# USB3_0_INTERFACE.net
KiCad netlist of a schematic drawn in Altium Designer
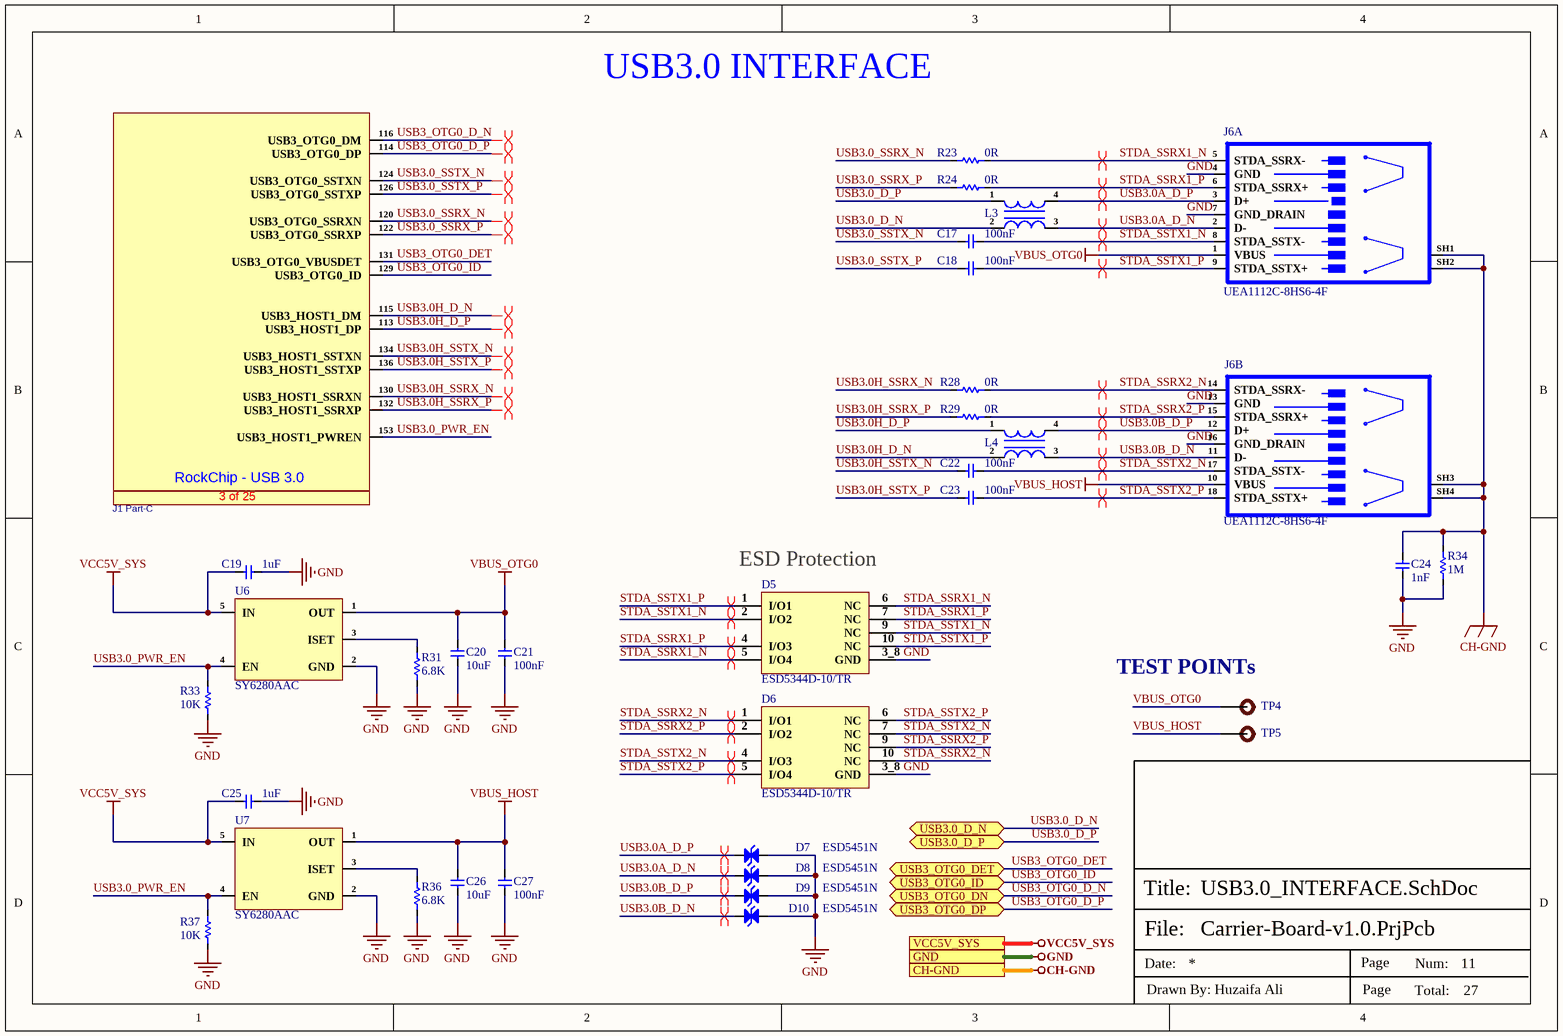
[diagram p0: USB3.0_INTERFACE.SchDoc]

(export (version "E")
  (design (tool "Eeschema 10.0.6"))
  (components
    (comp (ref "C17")
      (value "100nF")
      (footprint "Cap-0402")
      (description "CAP CER 0.1UF 16V X5R 0402")
      (fields
        (field (name "MANUFACTURER") "Yageo")
        (field (name "MANUFACTURER PART NUMBER") "CC0402KRX5R7BB104")
      )
      (libsource (lib "eSpark Libraries") (part "CC0402KRX5R7BB104"))
    )
    (comp (ref "C18")
      (value "100nF")
      (footprint "Cap-0402")
      (description "CAP CER 0.1UF 16V X5R 0402")
      (fields
        (field (name "MANUFACTURER") "Yageo")
        (field (name "MANUFACTURER PART NUMBER") "CC0402KRX5R7BB104")
      )
      (libsource (lib "eSpark Libraries") (part "CC0402KRX5R7BB104"))
    )
    (comp (ref "C19")
      (value "1uF")
      (footprint "Cap-0402")
      (description "CAP CER 1UF 16V X5R 0402")
      (fields
        (field (name "MANUFACTURER") "Yageo")
        (field (name "MANUFACTURER PART NUMBER") "CC0402KRX5R7BB105")
      )
      (libsource (lib "eSpark Libraries") (part "CC0402KRX5R7BB105"))
    )
    (comp (ref "C20")
      (value "10uF")
      (footprint "Cap-0603")
      (description "CAP CER 10UF 16V X5R 0603")
      (fields
        (field (name "MANUFACTURER") "Yageo")
        (field (name "MANUFACTURER PART NUMBER") "CC0603KRX5R7BB106")
      )
      (libsource (lib "eSpark Libraries") (part "CC0603KRX5R7BB106"))
    )
    (comp (ref "C21")
      (value "100nF")
      (footprint "Cap-0402")
      (description "CAP CER 0.1UF 16V X5R 0402")
      (fields
        (field (name "MANUFACTURER") "Yageo")
        (field (name "MANUFACTURER PART NUMBER") "CC0402KRX5R7BB104")
      )
      (libsource (lib "eSpark Libraries") (part "CC0402KRX5R7BB104"))
    )
    (comp (ref "C22")
      (value "100nF")
      (footprint "Cap-0402")
      (description "CAP CER 0.1UF 16V X5R 0402")
      (fields
        (field (name "MANUFACTURER") "Yageo")
        (field (name "MANUFACTURER PART NUMBER") "CC0402KRX5R7BB104")
      )
      (libsource (lib "eSpark Libraries") (part "CC0402KRX5R7BB104"))
    )
    (comp (ref "C23")
      (value "100nF")
      (footprint "Cap-0402")
      (description "CAP CER 0.1UF 16V X5R 0402")
      (fields
        (field (name "MANUFACTURER") "Yageo")
        (field (name "MANUFACTURER PART NUMBER") "CC0402KRX5R7BB104")
      )
      (libsource (lib "eSpark Libraries") (part "CC0402KRX5R7BB104"))
    )
    (comp (ref "C24")
      (value "1nF")
      (footprint "Cap-1206")
      (description "CAP CER 1000PF 2KV X7R 1206")
      (fields
        (field (name "MANUFACTURER") "Yageo")
        (field (name "MANUFACTURER PART NUMBER") "CC1206KKX7RDBB102")
      )
      (libsource (lib "eSpark Libraries") (part "CC1206KKX7RDBB102"))
    )
    (comp (ref "C25")
      (value "1uF")
      (footprint "Cap-0402")
      (description "CAP CER 1UF 16V X5R 0402")
      (fields
        (field (name "MANUFACTURER") "Yageo")
        (field (name "MANUFACTURER PART NUMBER") "CC0402KRX5R7BB105")
      )
      (libsource (lib "eSpark Libraries") (part "CC0402KRX5R7BB105"))
    )
    (comp (ref "C26")
      (value "10uF")
      (footprint "Cap-0603")
      (description "CAP CER 10UF 16V X5R 0603")
      (fields
        (field (name "MANUFACTURER") "Yageo")
        (field (name "MANUFACTURER PART NUMBER") "CC0603KRX5R7BB106")
      )
      (libsource (lib "eSpark Libraries") (part "CC0603KRX5R7BB106"))
    )
    (comp (ref "C27")
      (value "100nF")
      (footprint "Cap-0402")
      (description "CAP CER 0.1UF 16V X5R 0402")
      (fields
        (field (name "MANUFACTURER") "Yageo")
        (field (name "MANUFACTURER PART NUMBER") "CC0402KRX5R7BB104")
      )
      (libsource (lib "eSpark Libraries") (part "CC0402KRX5R7BB104"))
    )
    (comp (ref "D5")
      (value "ESD5344D-10/TR")
      (footprint "DFN2510-10L_")
      (description "DFN2510-10L ESD Protection Devices ROHS")
      (fields (field (name "MANUFACTURER") "WILLSEMI") (field (name "LCSC PART NUMBER") "C239666"))
      (libsource (lib "eSpark Libraries") (part "ESD5344D-10/TR"))
    )
    (comp (ref "D6")
      (value "ESD5344D-10/TR")
      (footprint "DFN2510-10L_")
      (description "DFN2510-10L ESD Protection Devices ROHS")
      (fields (field (name "MANUFACTURER") "WILLSEMI") (field (name "LCSC PART NUMBER") "C239666"))
      (libsource (lib "eSpark Libraries") (part "ESD5344D-10/TR"))
    )
    (comp (ref "D7")
      (value "ESD5451N")
      (footprint "DFN1006-2L (Bi-Directional)")
      (description "DFN1006-2(0402) ESD Protection Devices ROHS")
      (fields (field (name "MANUFACTURER") "TECH PUBLIC") (field (name "LCSC PART NUMBER") "C2936977"))
      (libsource (lib "Diode%") (part "ESD5451N"))
    )
    (comp (ref "D8")
      (value "ESD5451N")
      (footprint "DFN1006-2L (Bi-Directional)")
      (description "DFN1006-2(0402) ESD Protection Devices ROHS")
      (fields (field (name "MANUFACTURER") "TECH PUBLIC") (field (name "LCSC PART NUMBER") "C2936977"))
      (libsource (lib "Diode%") (part "ESD5451N"))
    )
    (comp (ref "D9")
      (value "ESD5451N")
      (footprint "DFN1006-2L (Bi-Directional)")
      (description "DFN1006-2(0402) ESD Protection Devices ROHS")
      (fields (field (name "MANUFACTURER") "TECH PUBLIC") (field (name "LCSC PART NUMBER") "C2936977"))
      (libsource (lib "Diode%") (part "ESD5451N"))
    )
    (comp (ref "D10")
      (value "ESD5451N")
      (footprint "DFN1006-2L (Bi-Directional)")
      (description "DFN1006-2(0402) ESD Protection Devices ROHS")
      (fields (field (name "MANUFACTURER") "TECH PUBLIC") (field (name "LCSC PART NUMBER") "C2936977"))
      (libsource (lib "Diode%") (part "ESD5451N"))
    )
    (comp (ref "J1 Part-")
      (value "AS0B826-S78B-7H")
      (footprint "AS0B826-S78B-7H")
      (description "SMD,P=0.5mm,Surface Mount，Right Angle")
      (fields (field (name "MANUFACTURER") "FOXCONN") (field (name "LCSC PART NUMBER") "C426232"))
      (libsource (lib "eSpark Libraries") (part "AS0B826-S78B-7H"))
    )
    (comp (ref "J6")
      (value "UEA1112C-8HS6-4F")
      (footprint "UEA1112C-8HS6-4F")
      (description "USB 3.0 2 Right-Angle 9P+9P Female Type-A Plugin USB Connectors ROHS")
      (fields (field (name "MANUFACTURER") "FOXCONN") (field (name "LCSC PART NUMBER") "C225759"))
      (libsource (lib "eSpark Libraries") (part "UEA1112C-8HS6-4F"))
    )
    (comp (ref "L3")
      (value "MCZ1210CH900L2TA0G")
      (footprint "MCZ1210CH900L2")
      (description "CMC 100MA 2LN 90 OHM SMD")
      (fields (field (name "MANUFACTURER") "TDK") (field (name "LCSC PART NUMBER") "C307688"))
      (libsource (lib "eSpark Libraries") (part "MCZ1210CH900L2TA0G"))
    )
    (comp (ref "L4")
      (value "MCZ1210CH900L2TA0G")
      (footprint "MCZ1210CH900L2")
      (description "CMC 100MA 2LN 90 OHM SMD")
      (fields (field (name "MANUFACTURER") "TDK") (field (name "LCSC PART NUMBER") "C307688"))
      (libsource (lib "eSpark Libraries") (part "MCZ1210CH900L2TA0G"))
    )
    (comp (ref "R23")
      (value "0R")
      (footprint "Res-0402")
      (description "RES 0 OHM JUMPER 1/16W 0402")
      (fields
        (field (name "MANUFACTURER") "Yageo")
        (field (name "MANUFACTURER PART NUMBER") "RC0402FR-070RL")
      )
      (libsource (lib "eSpark Libraries") (part "RC0402FR-070RL"))
    )
    (comp (ref "R24")
      (value "0R")
      (footprint "Res-0402")
      (description "RES 0 OHM JUMPER 1/16W 0402")
      (fields
        (field (name "MANUFACTURER") "Yageo")
        (field (name "MANUFACTURER PART NUMBER") "RC0402FR-070RL")
      )
      (libsource (lib "eSpark Libraries") (part "RC0402FR-070RL"))
    )
    (comp (ref "R28")
      (value "0R")
      (footprint "Res-0402")
      (description "RES 0 OHM JUMPER 1/16W 0402")
      (fields
        (field (name "MANUFACTURER") "Yageo")
        (field (name "MANUFACTURER PART NUMBER") "RC0402FR-070RL")
      )
      (libsource (lib "eSpark Libraries") (part "RC0402FR-070RL"))
    )
    (comp (ref "R29")
      (value "0R")
      (footprint "Res-0402")
      (description "RES 0 OHM JUMPER 1/16W 0402")
      (fields
        (field (name "MANUFACTURER") "Yageo")
        (field (name "MANUFACTURER PART NUMBER") "RC0402FR-070RL")
      )
      (libsource (lib "eSpark Libraries") (part "RC0402FR-070RL"))
    )
    (comp (ref "R31")
      (value "6.8K")
      (footprint "Res-0402")
      (description "RES 6.8K OHM 1% 1/16W 0402")
      (fields
        (field (name "MANUFACTURER") "Yageo")
        (field (name "MANUFACTURER PART NUMBER") "RC0402FR-076K8L")
      )
      (libsource (lib "eSpark Libraries") (part "RC0402FR-076K8L"))
    )
    (comp (ref "R33")
      (value "10K")
      (footprint "Res-0402")
      (description "RES 10K OHM 1% 1/16W 0402")
      (fields
        (field (name "MANUFACTURER") "Yageo")
        (field (name "MANUFACTURER PART NUMBER") "RC0402FR-0710KL")
      )
      (libsource (lib "eSpark Libraries") (part "RC0402FR-0710KL"))
    )
    (comp (ref "R34")
      (value "1M")
      (footprint "Res-0402")
      (description "RES SMD 1M OHM 5% 1/16W 0402")
      (fields
        (field (name "MANUFACTURER") "Yageo")
        (field (name "MANUFACTURER PART NUMBER") "AF0402JR-071ML")
      )
      (libsource (lib "eSpark Libraries") (part "AF0402JR-071ML"))
    )
    (comp (ref "R36")
      (value "6.8K")
      (footprint "Res-0402")
      (description "RES 6.8K OHM 1% 1/16W 0402")
      (fields
        (field (name "MANUFACTURER") "Yageo")
        (field (name "MANUFACTURER PART NUMBER") "RC0402FR-076K8L")
      )
      (libsource (lib "eSpark Libraries") (part "RC0402FR-076K8L"))
    )
    (comp (ref "R37")
      (value "10K")
      (footprint "Res-0402")
      (description "RES 10K OHM 1% 1/16W 0402")
      (fields
        (field (name "MANUFACTURER") "Yageo")
        (field (name "MANUFACTURER PART NUMBER") "RC0402FR-0710KL")
      )
      (libsource (lib "eSpark Libraries") (part "RC0402FR-0710KL"))
    )
    (comp (ref "TP4")
      (value "TEST POINT 0.5mm Dia")
      (footprint "Test-point - 0.5mm")
      (description "Test Point ON")
      (libsource (lib "eSpark Libraries") (part "TEST POINT 0.5mm Dia"))
    )
    (comp (ref "TP5")
      (value "TEST POINT 0.5mm Dia")
      (footprint "Test-point - 0.5mm")
      (description "Test Point ON")
      (libsource (lib "eSpark Libraries") (part "TEST POINT 0.5mm Dia"))
    )
    (comp (ref "U6")
      (value "SY6280AAC")
      (footprint "SOT-23-5")
      (description "SOT-23-5 Power Distribution Switches ROHS")
      (fields (field (name "MANUFACTURER") "Silergy") (field (name "LCSC PART NUMBER") "C55136"))
      (libsource (lib "eSpark Libraries") (part "SY6280AAC"))
    )
    (comp (ref "U7")
      (value "SY6280AAC")
      (footprint "SOT-23-5")
      (description "SOT-23-5 Power Distribution Switches ROHS")
      (fields (field (name "MANUFACTURER") "Silergy") (field (name "LCSC PART NUMBER") "C55136"))
      (libsource (lib "eSpark Libraries") (part "SY6280AAC"))
    )
  )
  (nets
    (net (code "1") (name "/STDA_SSRX1_N") (class "Default")
      (node (ref "D5") (pin "5") (pinfunction "I/O4_5") (pintype "passive"))
      (node (ref "D5") (pin "6") (pinfunction "NC_6") (pintype "passive"))
      (node (ref "J6") (pin "5") (pinfunction "STDA_SSRX-_5") (pintype "passive"))
      (node (ref "R23") (pin "2") (pinfunction "2_2") (pintype "passive"))
    )
    (net (code "2") (name "/STDA_SSRX1_P") (class "Default")
      (node (ref "D5") (pin "4") (pinfunction "I/O3_4") (pintype "passive"))
      (node (ref "D5") (pin "7") (pinfunction "NC_7") (pintype "passive"))
      (node (ref "J6") (pin "6") (pinfunction "STDA_SSRX+_6") (pintype "passive"))
      (node (ref "R24") (pin "2") (pinfunction "2_2") (pintype "passive"))
    )
    (net (code "3") (name "/STDA_SSRX2_N") (class "Default")
      (node (ref "D6") (pin "1") (pinfunction "I/O1_1") (pintype "passive"))
      (node (ref "D6") (pin "10") (pinfunction "NC_10") (pintype "passive"))
      (node (ref "J6") (pin "14") (pinfunction "STDA_SSRX-_14") (pintype "passive"))
      (node (ref "R28") (pin "2") (pinfunction "2_2") (pintype "passive"))
    )
    (net (code "4") (name "/STDA_SSRX2_P") (class "Default")
      (node (ref "D6") (pin "2") (pinfunction "I/O2_2") (pintype "passive"))
      (node (ref "D6") (pin "9") (pinfunction "NC_9") (pintype "passive"))
      (node (ref "J6") (pin "15") (pinfunction "STDA_SSRX+_15") (pintype "passive"))
      (node (ref "R29") (pin "2") (pinfunction "2_2") (pintype "passive"))
    )
    (net (code "5") (name "/STDA_SSTX1_N") (class "Default")
      (node (ref "C17") (pin "1") (pinfunction "1_1") (pintype "passive"))
      (node (ref "D5") (pin "2") (pinfunction "I/O2_2") (pintype "passive"))
      (node (ref "D5") (pin "9") (pinfunction "NC_9") (pintype "passive"))
      (node (ref "J6") (pin "8") (pinfunction "STDA_SSTX-_8") (pintype "passive"))
    )
    (net (code "6") (name "/STDA_SSTX1_P") (class "Default")
      (node (ref "C18") (pin "1") (pinfunction "1_1") (pintype "passive"))
      (node (ref "D5") (pin "1") (pinfunction "I/O1_1") (pintype "passive"))
      (node (ref "D5") (pin "10") (pinfunction "NC_10") (pintype "passive"))
      (node (ref "J6") (pin "9") (pinfunction "STDA_SSTX+_9") (pintype "passive"))
    )
    (net (code "7") (name "/STDA_SSTX2_N") (class "Default")
      (node (ref "C22") (pin "1") (pinfunction "1_1") (pintype "passive"))
      (node (ref "D6") (pin "4") (pinfunction "I/O3_4") (pintype "passive"))
      (node (ref "D6") (pin "7") (pinfunction "NC_7") (pintype "passive"))
      (node (ref "J6") (pin "17") (pinfunction "STDA_SSTX-_17") (pintype "passive"))
    )
    (net (code "8") (name "/STDA_SSTX2_P") (class "Default")
      (node (ref "C23") (pin "1") (pinfunction "1_1") (pintype "passive"))
      (node (ref "D6") (pin "5") (pinfunction "I/O4_5") (pintype "passive"))
      (node (ref "D6") (pin "6") (pinfunction "NC_6") (pintype "passive"))
      (node (ref "J6") (pin "18") (pinfunction "STDA_SSTX+_18") (pintype "passive"))
    )
    (net (code "9") (name "/USB3.0A_D_N") (class "Default")
      (node (ref "D8") (pin "2") (pinfunction "K_2") (pintype "passive"))
      (node (ref "J6") (pin "2") (pinfunction "D-_2") (pintype "passive"))
      (node (ref "L3") (pin "3") (pinfunction "3_3") (pintype "passive"))
    )
    (net (code "10") (name "/USB3.0A_D_P") (class "Default")
      (node (ref "D7") (pin "2") (pinfunction "K_2") (pintype "passive"))
      (node (ref "J6") (pin "3") (pinfunction "D+_3") (pintype "passive"))
      (node (ref "L3") (pin "4") (pinfunction "4_4") (pintype "passive"))
    )
    (net (code "11") (name "/USB3.0B_D_N") (class "Default")
      (node (ref "D10") (pin "2") (pinfunction "K_2") (pintype "passive"))
      (node (ref "J6") (pin "11") (pinfunction "D-_11") (pintype "passive"))
      (node (ref "L4") (pin "3") (pinfunction "3_3") (pintype "passive"))
    )
    (net (code "12") (name "/USB3.0B_D_P") (class "Default")
      (node (ref "D9") (pin "2") (pinfunction "K_2") (pintype "passive"))
      (node (ref "J6") (pin "12") (pinfunction "D+_12") (pintype "passive"))
      (node (ref "L4") (pin "4") (pinfunction "4_4") (pintype "passive"))
    )
    (net (code "13") (name "/USB3.0H_D_N") (class "Default")
      (node (ref "J1 Part-") (pin "115") (pinfunction "USB3_HOST1_DM_115") (pintype "passive"))
      (node (ref "L4") (pin "2") (pinfunction "2_2") (pintype "passive"))
    )
    (net (code "14") (name "/USB3.0H_D_P") (class "Default")
      (node (ref "J1 Part-") (pin "113") (pinfunction "USB3_HOST1_DP_113") (pintype "passive"))
      (node (ref "L4") (pin "1") (pinfunction "1_1") (pintype "passive"))
    )
    (net (code "15") (name "/USB3.0H_SSRX_N") (class "Default")
      (node (ref "J1 Part-") (pin "130") (pinfunction "USB3_HOST1_SSRXN_130") (pintype "passive"))
      (node (ref "R28") (pin "1") (pinfunction "1_1") (pintype "passive"))
    )
    (net (code "16") (name "/USB3.0H_SSRX_P") (class "Default")
      (node (ref "J1 Part-") (pin "132") (pinfunction "USB3_HOST1_SSRXP_132") (pintype "passive"))
      (node (ref "R29") (pin "1") (pinfunction "1_1") (pintype "passive"))
    )
    (net (code "17") (name "/USB3.0H_SSTX_N") (class "Default")
      (node (ref "C22") (pin "2") (pinfunction "2_2") (pintype "passive"))
      (node (ref "J1 Part-") (pin "134") (pinfunction "USB3_HOST1_SSTXN_134") (pintype "passive"))
    )
    (net (code "18") (name "/USB3.0H_SSTX_P") (class "Default")
      (node (ref "C23") (pin "2") (pinfunction "2_2") (pintype "passive"))
      (node (ref "J1 Part-") (pin "136") (pinfunction "USB3_HOST1_SSTXP_136") (pintype "passive"))
    )
    (net (code "19") (name "/USB3.0_D_N") (class "Default")
      (node (ref "L3") (pin "2") (pinfunction "2_2") (pintype "passive"))
    )
    (net (code "20") (name "/USB3.0_D_P") (class "Default")
      (node (ref "L3") (pin "1") (pinfunction "1_1") (pintype "passive"))
    )
    (net (code "21") (name "/USB3.0_PWR_EN") (class "Default")
      (node (ref "J1 Part-") (pin "153") (pinfunction "USB3_HOST1_PWREN_153") (pintype "passive"))
      (node (ref "R33") (pin "2") (pinfunction "2_2") (pintype "passive"))
      (node (ref "R37") (pin "2") (pinfunction "2_2") (pintype "passive"))
      (node (ref "U6") (pin "4") (pinfunction "EN_4") (pintype "passive"))
      (node (ref "U7") (pin "4") (pinfunction "EN_4") (pintype "passive"))
    )
    (net (code "22") (name "/USB3.0_SSRX_N") (class "Default")
      (node (ref "J1 Part-") (pin "120") (pinfunction "USB3_OTG0_SSRXN_120") (pintype "passive"))
      (node (ref "R23") (pin "1") (pinfunction "1_1") (pintype "passive"))
    )
    (net (code "23") (name "/USB3.0_SSRX_P") (class "Default")
      (node (ref "J1 Part-") (pin "122") (pinfunction "USB3_OTG0_SSRXP_122") (pintype "passive"))
      (node (ref "R24") (pin "1") (pinfunction "1_1") (pintype "passive"))
    )
    (net (code "24") (name "/USB3.0_SSTX_N") (class "Default")
      (node (ref "C17") (pin "2") (pinfunction "2_2") (pintype "passive"))
      (node (ref "J1 Part-") (pin "124") (pinfunction "USB3_OTG0_SSTXN_124") (pintype "passive"))
    )
    (net (code "25") (name "/USB3.0_SSTX_P") (class "Default")
      (node (ref "C18") (pin "2") (pinfunction "2_2") (pintype "passive"))
      (node (ref "J1 Part-") (pin "126") (pinfunction "USB3_OTG0_SSTXP_126") (pintype "passive"))
    )
    (net (code "26") (name "/USB3_OTG0_DET") (class "Default")
      (node (ref "J1 Part-") (pin "131") (pinfunction "USB3_OTG0_VBUSDET_131") (pintype "passive"))
    )
    (net (code "27") (name "/USB3_OTG0_D_N") (class "Default")
      (node (ref "J1 Part-") (pin "116") (pinfunction "USB3_OTG0_DM_116") (pintype "passive"))
    )
    (net (code "28") (name "/USB3_OTG0_D_P") (class "Default")
      (node (ref "J1 Part-") (pin "114") (pinfunction "USB3_OTG0_DP_114") (pintype "passive"))
    )
    (net (code "29") (name "/USB3_OTG0_ID") (class "Default")
      (node (ref "J1 Part-") (pin "129") (pinfunction "USB3_OTG0_ID_129") (pintype "passive"))
    )
    (net (code "30") (name "CH-GND") (class "Default")
      (node (ref "C24") (pin "2") (pinfunction "2_2") (pintype "passive"))
      (node (ref "J6") (pin "SH1") (pinfunction "GND_SH1") (pintype "passive"))
      (node (ref "J6") (pin "SH2") (pinfunction "GND_SH2") (pintype "passive"))
      (node (ref "J6") (pin "SH3") (pinfunction "GND_SH3") (pintype "passive"))
      (node (ref "J6") (pin "SH4") (pinfunction "GND_SH4") (pintype "passive"))
      (node (ref "R34") (pin "2") (pinfunction "2_2") (pintype "passive"))
    )
    (net (code "31") (name "GND") (class "Default")
      (node (ref "C19") (pin "1") (pinfunction "1_1") (pintype "passive"))
      (node (ref "C20") (pin "1") (pinfunction "1_1") (pintype "passive"))
      (node (ref "C21") (pin "1") (pinfunction "1_1") (pintype "passive"))
      (node (ref "C24") (pin "1") (pinfunction "1_1") (pintype "passive"))
      (node (ref "C25") (pin "1") (pinfunction "1_1") (pintype "passive"))
      (node (ref "C26") (pin "1") (pinfunction "1_1") (pintype "passive"))
      (node (ref "C27") (pin "1") (pinfunction "1_1") (pintype "passive"))
      (node (ref "D10") (pin "1") (pinfunction "K_1") (pintype "passive"))
      (node (ref "D5") (pin "3_8") (pinfunction "GND_3_8") (pintype "passive"))
      (node (ref "D6") (pin "3_8") (pinfunction "GND_3_8") (pintype "passive"))
      (node (ref "D7") (pin "1") (pinfunction "K_1") (pintype "passive"))
      (node (ref "D8") (pin "1") (pinfunction "K_1") (pintype "passive"))
      (node (ref "D9") (pin "1") (pinfunction "K_1") (pintype "passive"))
      (node (ref "J6") (pin "13") (pinfunction "GND_13") (pintype "passive"))
      (node (ref "J6") (pin "16") (pinfunction "GND_DRAIN_16") (pintype "passive"))
      (node (ref "J6") (pin "4") (pinfunction "GND_4") (pintype "passive"))
      (node (ref "J6") (pin "7") (pinfunction "GND_DRAIN_7") (pintype "passive"))
      (node (ref "R31") (pin "1") (pinfunction "1_1") (pintype "passive"))
      (node (ref "R33") (pin "1") (pinfunction "1_1") (pintype "passive"))
      (node (ref "R34") (pin "1") (pinfunction "1_1") (pintype "passive"))
      (node (ref "R36") (pin "1") (pinfunction "1_1") (pintype "passive"))
      (node (ref "R37") (pin "1") (pinfunction "1_1") (pintype "passive"))
      (node (ref "U6") (pin "2") (pinfunction "GND_2") (pintype "passive"))
      (node (ref "U7") (pin "2") (pinfunction "GND_2") (pintype "passive"))
    )
    (net (code "32") (name "Net-(U6-ISET)") (class "Default")
      (node (ref "R31") (pin "2") (pinfunction "2_2") (pintype "passive"))
      (node (ref "U6") (pin "3") (pinfunction "ISET_3") (pintype "passive"))
    )
    (net (code "33") (name "Net-(U7-ISET)") (class "Default")
      (node (ref "R36") (pin "2") (pinfunction "2_2") (pintype "passive"))
      (node (ref "U7") (pin "3") (pinfunction "ISET_3") (pintype "passive"))
    )
    (net (code "34") (name "VBUS_HOST") (class "Default")
      (node (ref "C26") (pin "2") (pinfunction "2_2") (pintype "passive"))
      (node (ref "C27") (pin "2") (pinfunction "2_2") (pintype "passive"))
      (node (ref "J6") (pin "10") (pinfunction "VBUS_10") (pintype "passive"))
      (node (ref "TP5") (pin "1") (pinfunction "1_1") (pintype "passive"))
      (node (ref "U7") (pin "1") (pinfunction "OUT_1") (pintype "passive"))
    )
    (net (code "35") (name "VBUS_OTG0") (class "Default")
      (node (ref "C20") (pin "2") (pinfunction "2_2") (pintype "passive"))
      (node (ref "C21") (pin "2") (pinfunction "2_2") (pintype "passive"))
      (node (ref "J6") (pin "1") (pinfunction "VBUS_1") (pintype "passive"))
      (node (ref "TP4") (pin "1") (pinfunction "1_1") (pintype "passive"))
      (node (ref "U6") (pin "1") (pinfunction "OUT_1") (pintype "passive"))
    )
    (net (code "36") (name "VCC5V_SYS") (class "Default")
      (node (ref "C19") (pin "2") (pinfunction "2_2") (pintype "passive"))
      (node (ref "C25") (pin "2") (pinfunction "2_2") (pintype "passive"))
      (node (ref "U6") (pin "5") (pinfunction "IN_5") (pintype "passive"))
      (node (ref "U7") (pin "5") (pinfunction "IN_5") (pintype "passive"))
    )
  )
)
